# Mergen_Ground_Station_V2_0.net
KiCad netlist of a schematic drawn in EAGLE
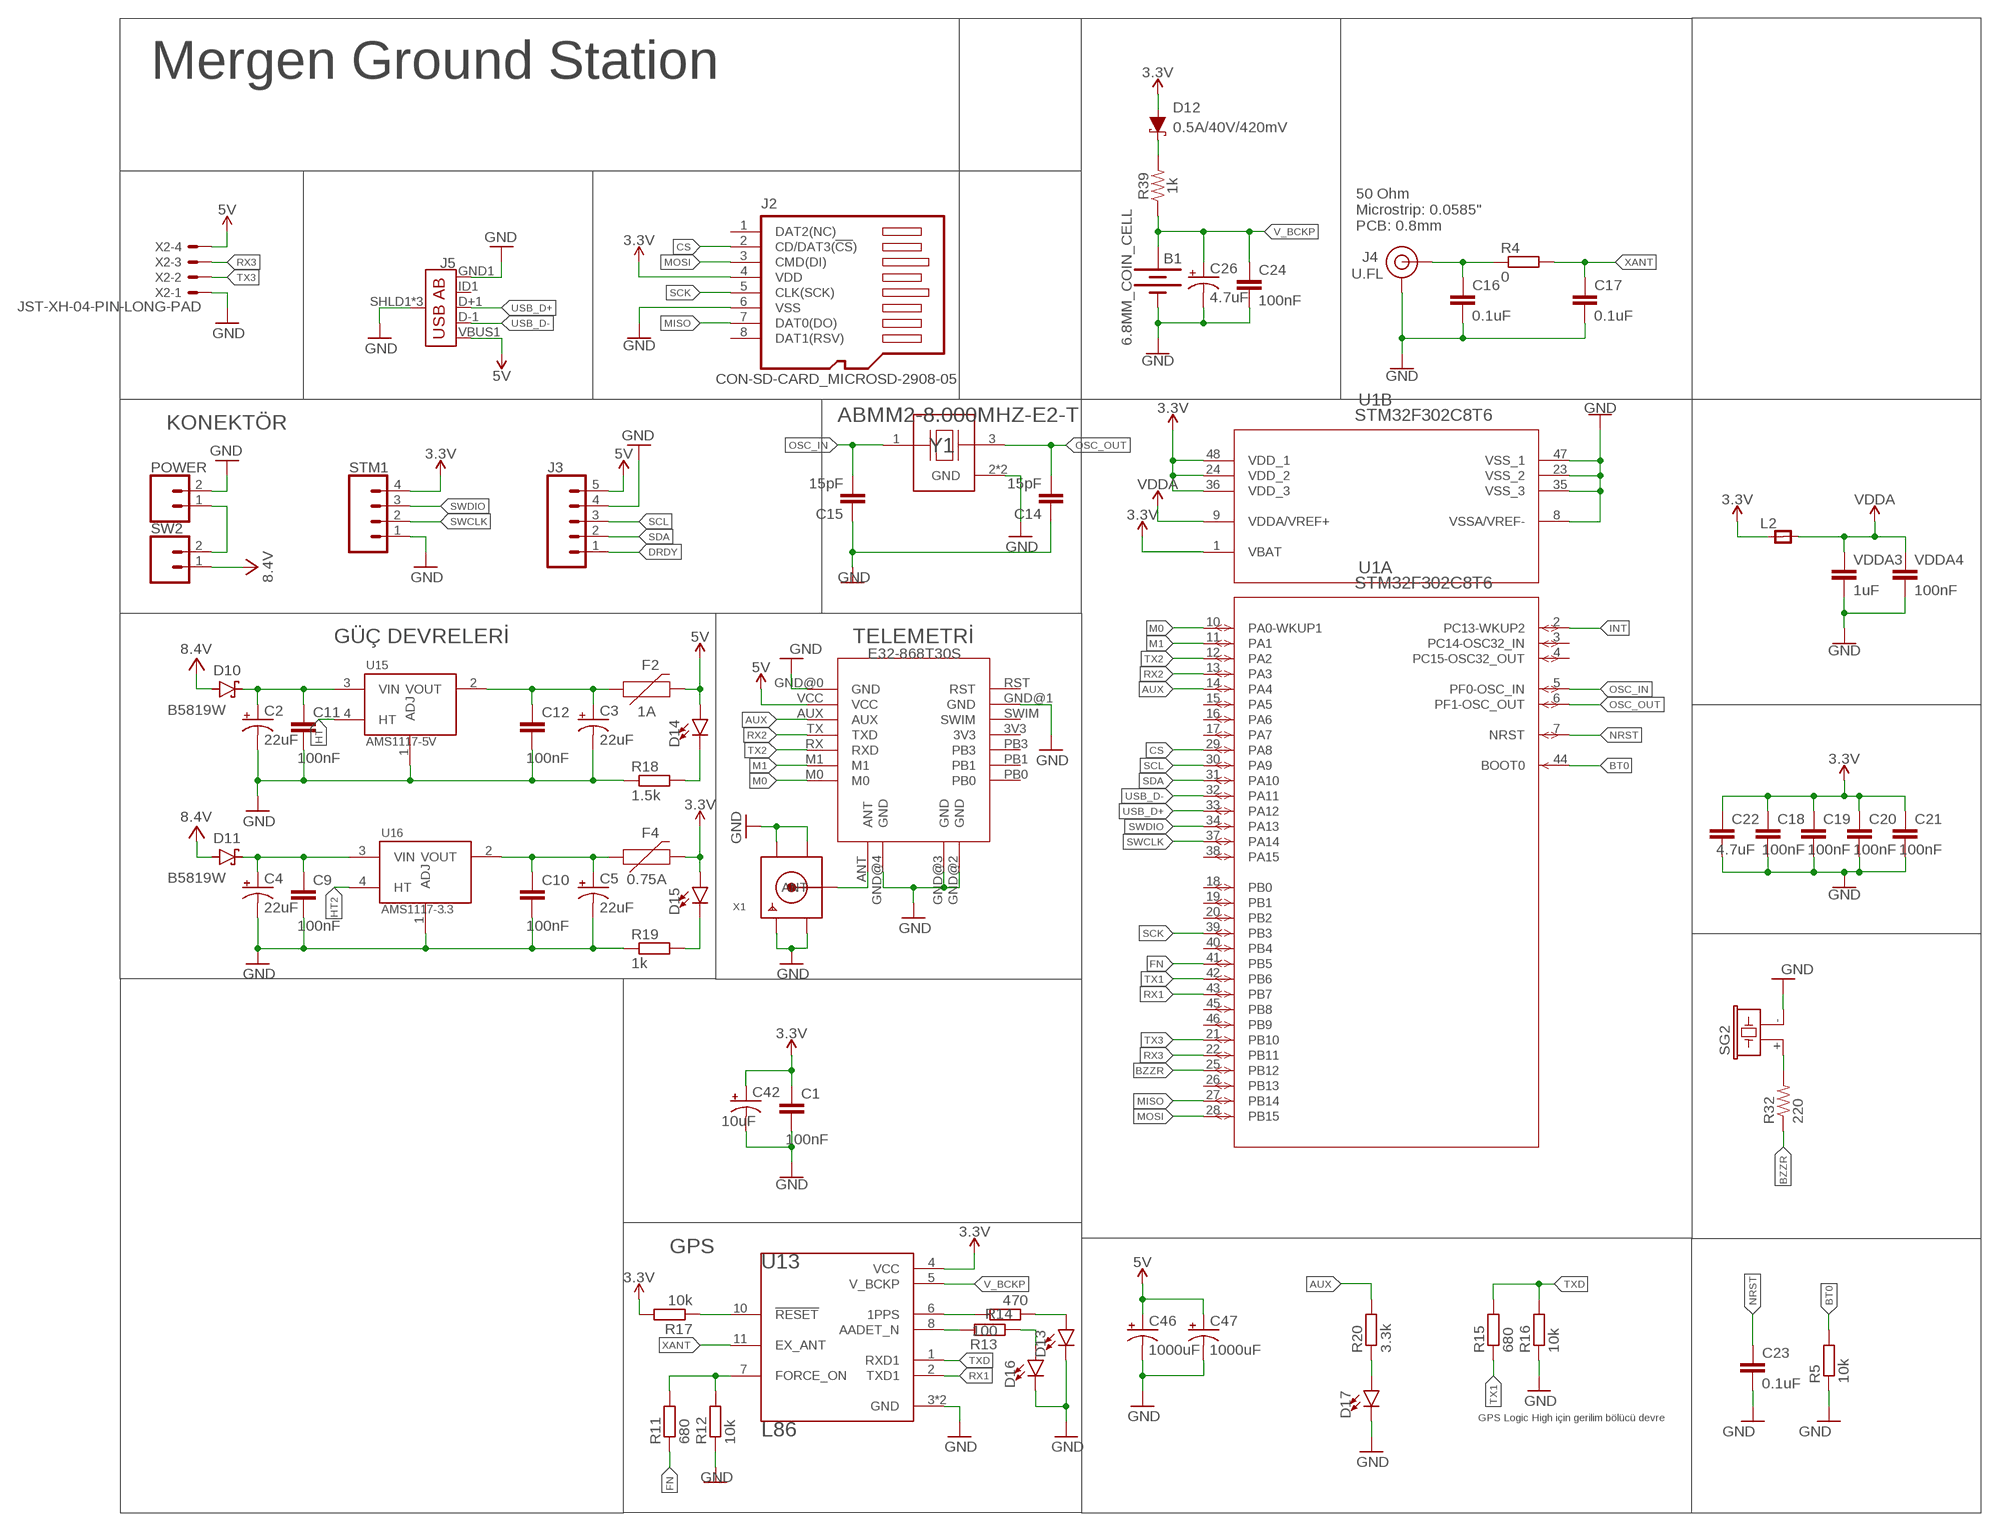
[diagram p0: schematic, sheet 1]

(export (version "E")
  (design (tool "Eeschema 10.0.6"))
  (components
    (comp (ref "B1")
      (value "6.8MM_COIN_CELL")
      (footprint "eagle-import:BATTCON-6.8MM")
      (libsource (lib "eagle-import") (part "BATTERY-6.8MM_SMD"))
    )
    (comp (ref "C1")
      (value "100nF")
      (footprint "eagle-import:C0603")
      (libsource (lib "eagle-import") (part "C-EUC0603"))
    )
    (comp (ref "C2")
      (value "22uF")
      (footprint "eagle-import:CT3528")
      (libsource (lib "eagle-import") (part "rcl_334_CPOL-USCT3528"))
    )
    (comp (ref "C3")
      (value "22uF")
      (footprint "eagle-import:CT3528")
      (libsource (lib "eagle-import") (part "rcl_334_CPOL-USCT3528"))
    )
    (comp (ref "C4")
      (value "22uF")
      (footprint "eagle-import:CT3528")
      (libsource (lib "eagle-import") (part "rcl_334_CPOL-USCT3528"))
    )
    (comp (ref "C5")
      (value "22uF")
      (footprint "eagle-import:CT3528")
      (libsource (lib "eagle-import") (part "rcl_334_CPOL-USCT3528"))
    )
    (comp (ref "C9")
      (value "100nF")
      (footprint "eagle-import:C0603")
      (libsource (lib "eagle-import") (part "C-EUC0603"))
    )
    (comp (ref "C10")
      (value "100nF")
      (footprint "eagle-import:C0603")
      (libsource (lib "eagle-import") (part "C-EUC0603"))
    )
    (comp (ref "C11")
      (value "100nF")
      (footprint "eagle-import:C0603")
      (libsource (lib "eagle-import") (part "C-EUC0603"))
    )
    (comp (ref "C12")
      (value "100nF")
      (footprint "eagle-import:C0603")
      (libsource (lib "eagle-import") (part "C-EUC0603"))
    )
    (comp (ref "C14")
      (value "15pF")
      (footprint "eagle-import:C0603")
      (libsource (lib "eagle-import") (part "C-EUC0603"))
    )
    (comp (ref "C15")
      (value "15pF")
      (footprint "eagle-import:C0603")
      (libsource (lib "eagle-import") (part "C-EUC0603"))
    )
    (comp (ref "C16")
      (value "0.1uF")
      (footprint "eagle-import:C0603")
      (libsource (lib "eagle-import") (part "C-EUC0603"))
    )
    (comp (ref "C17")
      (value "0.1uF")
      (footprint "eagle-import:C0603")
      (libsource (lib "eagle-import") (part "C-EUC0603"))
    )
    (comp (ref "C18")
      (value "100nF")
      (footprint "eagle-import:C0603")
      (libsource (lib "eagle-import") (part "C-EUC0603"))
    )
    (comp (ref "C19")
      (value "100nF")
      (footprint "eagle-import:C0603")
      (libsource (lib "eagle-import") (part "C-EUC0603"))
    )
    (comp (ref "C20")
      (value "100nF")
      (footprint "eagle-import:C0603")
      (libsource (lib "eagle-import") (part "C-EUC0603"))
    )
    (comp (ref "C21")
      (value "100nF")
      (footprint "eagle-import:C0603")
      (libsource (lib "eagle-import") (part "C-EUC0603"))
    )
    (comp (ref "C22")
      (value "4.7uF")
      (footprint "eagle-import:C0603")
      (libsource (lib "eagle-import") (part "C-EUC0603"))
    )
    (comp (ref "C23")
      (value "0.1uF")
      (footprint "eagle-import:C0603")
      (libsource (lib "eagle-import") (part "C-EUC0603"))
    )
    (comp (ref "C24")
      (value "100nF")
      (footprint "eagle-import:C0603")
      (libsource (lib "eagle-import") (part "C-EUC0603"))
    )
    (comp (ref "C26")
      (value "4.7uF")
      (footprint "eagle-import:A_3216-18R")
      (libsource (lib "eagle-import") (part "rcl_334_CPOL-USA/3216-18R"))
    )
    (comp (ref "C42")
      (value "10uF")
      (footprint "eagle-import:EIA3216")
      (libsource (lib "eagle-import") (part "10UF-POLAR-EIA3216-16V-10%(TANT)"))
    )
    (comp (ref "C46")
      (value "1000uF")
      (footprint "eagle-import:150CLZ-1010")
      (libsource (lib "eagle-import") (part "CPOL-US150CLZ-1010"))
    )
    (comp (ref "C47")
      (value "1000uF")
      (footprint "eagle-import:150CLZ-1010")
      (libsource (lib "eagle-import") (part "CPOL-US150CLZ-1010"))
    )
    (comp (ref "D10")
      (value "B5819W")
      (footprint "eagle-import:SODFL3718X115")
      (fields (field (name "MANUFACTURER") "ON Semiconductor") (field (name "MPN") "MBR0520LT1G"))
      (libsource (lib "eagle-import") (part "SCHOTTKY_DO-219MBR0520LT1G"))
    )
    (comp (ref "D11")
      (value "B5819W")
      (footprint "eagle-import:SODFL3718X115")
      (fields (field (name "MANUFACTURER") "ON Semiconductor") (field (name "MPN") "MBR0520LT1G"))
      (libsource (lib "eagle-import") (part "SCHOTTKY_DO-219MBR0520LT1G"))
    )
    (comp (ref "D12")
      (value "0.5A/40V/420mV")
      (footprint "eagle-import:SOD-323")
      (libsource (lib "eagle-import") (part "DIODE-SCHOTTKY-PMEG4005EJ"))
    )
    (comp (ref "D13")
      (value "LED0603")
      (footprint "eagle-import:LED-0603")
      (libsource (lib "eagle-import") (part "LED0603"))
    )
    (comp (ref "D14")
      (value "LED0603")
      (footprint "eagle-import:LED-0603")
      (libsource (lib "eagle-import") (part "LED0603"))
    )
    (comp (ref "D15")
      (value "LED0603")
      (footprint "eagle-import:LED-0603")
      (libsource (lib "eagle-import") (part "LED0603"))
    )
    (comp (ref "D16")
      (value "LED0603")
      (footprint "eagle-import:LED-0603")
      (libsource (lib "eagle-import") (part "LED0603"))
    )
    (comp (ref "D17")
      (value "LED0603")
      (footprint "eagle-import:LED-0603")
      (libsource (lib "eagle-import") (part "LED0603"))
    )
    (comp (ref "F2")
      (value "1A")
      (footprint "eagle-import:1206")
      (libsource (lib "eagle-import") (part "PPTC_HALF-AMP"))
    )
    (comp (ref "F4")
      (value "0.75A")
      (footprint "eagle-import:1206")
      (libsource (lib "eagle-import") (part "PPTC_HALF-AMP"))
    )
    (comp (ref "J2")
      (value "CON-SD-CARD_MICROSD-2908-05")
      (footprint "eagle-import:CON-SD-CARD_2908-05")
      (libsource (lib "eagle-import") (part "CON-SD-CARD_MICROSD-2908-05"))
    )
    (comp (ref "J3")
      (value "CONN_05LOCK_LONGPADS")
      (footprint "eagle-import:1X05_LOCK_LONGPADS")
      (libsource (lib "eagle-import") (part "CONN_05LOCK_LONGPADS"))
    )
    (comp (ref "J4")
      (value "U.FL")
      (footprint "eagle-import:U.FL")
      (libsource (lib "eagle-import") (part "U.FL2PIN"))
    )
    (comp (ref "J5")
      (value "USB_AB_SMT")
      (footprint "eagle-import:USB-AB-MICRO-SMD")
      (libsource (lib "eagle-import") (part "USB_AB_SMT"))
    )
    (comp (ref "L2")
      (value "RC-MASTER-SMD_FB_0805MP")
      (footprint "eagle-import:RC-MASTER-SMD_L0805MP")
      (libsource (lib "eagle-import") (part "RC-MASTER-SMD_FB_0805MP"))
    )
    (comp (ref "POWER")
      (value "CONN_023.5MM-NO_SILK")
      (footprint "eagle-import:SCREWTERMINAL-3.5MM-2-NS")
      (libsource (lib "eagle-import") (part "CONN_023.5MM-NO_SILK"))
    )
    (comp (ref "R4")
      (value "0")
      (footprint "eagle-import:R0603")
      (libsource (lib "eagle-import") (part "R-EU_R0603"))
    )
    (comp (ref "R5")
      (value "10k")
      (footprint "eagle-import:R0603")
      (libsource (lib "eagle-import") (part "R-EU_R0603"))
    )
    (comp (ref "R11")
      (value "680")
      (footprint "eagle-import:R0603")
      (libsource (lib "eagle-import") (part "R-EU_R0603"))
    )
    (comp (ref "R12")
      (value "10k")
      (footprint "eagle-import:R0603")
      (libsource (lib "eagle-import") (part "R-EU_R0603"))
    )
    (comp (ref "R13")
      (value "100")
      (footprint "eagle-import:R0603")
      (libsource (lib "eagle-import") (part "R-EU_R0603"))
    )
    (comp (ref "R14")
      (value "470")
      (footprint "eagle-import:R0603")
      (libsource (lib "eagle-import") (part "R-EU_R0603"))
    )
    (comp (ref "R15")
      (value "680")
      (footprint "eagle-import:R0603")
      (libsource (lib "eagle-import") (part "R-EU_R0603"))
    )
    (comp (ref "R16")
      (value "10k")
      (footprint "eagle-import:R0603")
      (libsource (lib "eagle-import") (part "R-EU_R0603"))
    )
    (comp (ref "R17")
      (value "10k")
      (footprint "eagle-import:R0603")
      (libsource (lib "eagle-import") (part "R-EU_R0603"))
    )
    (comp (ref "R18")
      (value "1.5k")
      (footprint "eagle-import:R0603")
      (libsource (lib "eagle-import") (part "R-EU_R0603"))
    )
    (comp (ref "R19")
      (value "1k")
      (footprint "eagle-import:R0603")
      (libsource (lib "eagle-import") (part "R-EU_R0603"))
    )
    (comp (ref "R20")
      (value "3.3k")
      (footprint "eagle-import:R0603")
      (libsource (lib "eagle-import") (part "R-EU_R0603"))
    )
    (comp (ref "R32")
      (value "220")
      (footprint "eagle-import:0603")
      (libsource (lib "eagle-import") (part "0OHM-0603-1/10W-5%"))
    )
    (comp (ref "R39")
      (value "1k")
      (footprint "eagle-import:0603")
      (libsource (lib "eagle-import") (part "1KOHM-0603-1/10W-1%"))
    )
    (comp (ref "SG2")
      (value "F/CM12P")
      (footprint "eagle-import:F_CM12P")
      (libsource (lib "eagle-import") (part "F/CM12P"))
    )
    (comp (ref "STM1")
      (value "CONN_04")
      (footprint "eagle-import:1X04")
      (libsource (lib "eagle-import") (part "CONN_04"))
    )
    (comp (ref "SW2")
      (value "CONN_023.5MM-NO_SILK")
      (footprint "eagle-import:SCREWTERMINAL-3.5MM-2-NS")
      (libsource (lib "eagle-import") (part "CONN_023.5MM-NO_SILK"))
    )
    (comp (ref "U1")
      (value "STM32F302C8T6")
      (footprint "eagle-import:LQFP48-7X7MM")
      (fields (field (name "COPYRIGHT") "Copyright (C) 2018 Accelerated Designs. All rights reserved"))
      (libsource (lib "eagle-import") (part "STM32F302C8T6"))
    )
    (comp (ref "U13")
      (value "L86")
      (footprint "eagle-import:XCVR_L86")
      (fields (field (name "MF") "Quectel"))
      (libsource (lib "eagle-import") (part "L86"))
    )
    (comp (ref "U14")
      (value "E32-868T30S")
      (footprint "eagle-import:E32-868T30S")
      (libsource (lib "eagle-import") (part "E32-868T30S"))
    )
    (comp (ref "U15")
      (value "AMS1117-5V")
      (footprint "eagle-import:SOT229P700X180-4N")
      (fields (field (name "MF") "Advanced Monolithic Systems") (field (name "MP") "AMS1117-3.3"))
      (libsource (lib "eagle-import") (part "AMS1117-3.3"))
    )
    (comp (ref "U16")
      (value "AMS1117-3.3")
      (footprint "eagle-import:SOT229P700X180-4N")
      (fields (field (name "MF") "Advanced Monolithic Systems"))
      (libsource (lib "eagle-import") (part "AMS1117-3.3"))
    )
    (comp (ref "VDDA3")
      (value "1uF")
      (footprint "eagle-import:0603")
      (libsource (lib "eagle-import") (part "0.1UF-0603-25V-(+80/-20%)"))
    )
    (comp (ref "VDDA4")
      (value "100nF")
      (footprint "eagle-import:0603")
      (libsource (lib "eagle-import") (part "0.1UF-0603-25V-(+80/-20%)"))
    )
    (comp (ref "X1")
      (value "SMACONNECTOR")
      (footprint "eagle-import:SMA90_DIP")
      (libsource (lib "eagle-import") (part "SMACONNECTOR"))
    )
    (comp (ref "X2")
      (value "JST-XH-04-PIN-LONG-PAD")
      (footprint "eagle-import:JST-XH-04-PACKAGE-LONG-PAD")
      (libsource (lib "eagle-import") (part "JST-XH-04-PIN-LONG-PAD"))
    )
    (comp (ref "Y1")
      (value "ABMM2-8.000MHZ-E2-T")
      (footprint "eagle-import:XTAL_ABMM2-8.000MHZ-E2-T")
      (fields (field (name "MF") "Abracon"))
      (libsource (lib "eagle-import") (part "ABMM2-8.000MHZ-E2-T"))
    )
  )
  (nets
    (net (code "1") (name "3.3V") (class "Default")
      (node (ref "C1") (pin "1") (pinfunction "1_1") (pintype "passive"))
      (node (ref "C18") (pin "1") (pinfunction "1_1") (pintype "passive"))
      (node (ref "C19") (pin "1") (pinfunction "1_1") (pintype "passive"))
      (node (ref "C20") (pin "1") (pinfunction "1_1") (pintype "passive"))
      (node (ref "C21") (pin "1") (pinfunction "1_1") (pintype "passive"))
      (node (ref "C22") (pin "1") (pinfunction "1_1") (pintype "passive"))
      (node (ref "C42") (pin "+") (pinfunction "+_+") (pintype "passive"))
      (node (ref "D12") (pin "A") (pinfunction "A_A") (pintype "passive"))
      (node (ref "D15") (pin "A") (pinfunction "A_A") (pintype "passive"))
      (node (ref "F4") (pin "2") (pinfunction "2_2") (pintype "bidirectional"))
      (node (ref "J2") (pin "4") (pinfunction "VDD_4") (pintype "bidirectional"))
      (node (ref "L2") (pin "1") (pinfunction "1_1") (pintype "passive"))
      (node (ref "R17") (pin "2") (pinfunction "2_2") (pintype "passive"))
      (node (ref "STM1") (pin "4") (pinfunction "4_4") (pintype "passive"))
      (node (ref "U1") (pin "1") (pinfunction "VBAT_1") (pintype "power_in"))
      (node (ref "U1") (pin "24") (pinfunction "VDD_2_24") (pintype "power_in"))
      (node (ref "U1") (pin "36") (pinfunction "VDD_3_36") (pintype "power_in"))
      (node (ref "U1") (pin "48") (pinfunction "VDD_1_48") (pintype "power_in"))
      (node (ref "U13") (pin "4") (pinfunction "VCC_4") (pintype "power_in"))
    )
    (net (code "2") (name "5V") (class "Default")
      (node (ref "C46") (pin "+") (pinfunction "+_+") (pintype "passive"))
      (node (ref "C47") (pin "+") (pinfunction "+_+") (pintype "passive"))
      (node (ref "D14") (pin "A") (pinfunction "A_A") (pintype "passive"))
      (node (ref "F2") (pin "2") (pinfunction "2_2") (pintype "bidirectional"))
      (node (ref "J3") (pin "5") (pinfunction "5_5") (pintype "passive"))
      (node (ref "J5") (pin "VBUS1") (pinfunction "VBUS_VBUS1") (pintype "power_in"))
      (node (ref "U14") (pin "VCC") (pinfunction "VCC_VCC") (pintype "bidirectional"))
      (node (ref "X2") (pin "4") (pinfunction "S_4") (pintype "passive"))
    )
    (net (code "3") (name "8.4V") (class "Default")
      (node (ref "D10") (pin "2") (pinfunction "A_2") (pintype "passive"))
      (node (ref "D11") (pin "2") (pinfunction "A_2") (pintype "passive"))
      (node (ref "SW2") (pin "1") (pinfunction "1_1") (pintype "passive"))
    )
    (net (code "4") (name "AUX") (class "Default")
      (node (ref "R20") (pin "2") (pinfunction "2_2") (pintype "passive"))
      (node (ref "U1") (pin "14") (pinfunction "PA4_14") (pintype "bidirectional"))
      (node (ref "U14") (pin "AUX") (pinfunction "AUX_AUX") (pintype "bidirectional"))
    )
    (net (code "5") (name "BT0") (class "Default")
      (node (ref "R5") (pin "2") (pinfunction "2_2") (pintype "passive"))
      (node (ref "U1") (pin "44") (pinfunction "BOOT0_44") (pintype "input"))
    )
    (net (code "6") (name "BZZR") (class "Default")
      (node (ref "R32") (pin "1") (pinfunction "1_1") (pintype "passive"))
      (node (ref "U1") (pin "25") (pinfunction "PB12_25") (pintype "bidirectional"))
    )
    (net (code "7") (name "CS") (class "Default")
      (node (ref "J2") (pin "2") (pinfunction "CD/DAT3(~{CS})_2") (pintype "bidirectional"))
      (node (ref "U1") (pin "29") (pinfunction "PA8_29") (pintype "bidirectional"))
    )
    (net (code "8") (name "DRDY") (class "Default")
      (node (ref "J3") (pin "1") (pinfunction "1_1") (pintype "passive"))
    )
    (net (code "9") (name "FN") (class "Default")
      (node (ref "R11") (pin "1") (pinfunction "1_1") (pintype "passive"))
      (node (ref "U1") (pin "41") (pinfunction "PB5_41") (pintype "bidirectional"))
    )
    (net (code "10") (name "GND") (class "Default")
      (node (ref "B1") (pin "-") (pinfunction "-_-") (pintype "power_in"))
      (node (ref "C1") (pin "2") (pinfunction "2_2") (pintype "passive"))
      (node (ref "C10") (pin "2") (pinfunction "2_2") (pintype "passive"))
      (node (ref "C11") (pin "2") (pinfunction "2_2") (pintype "passive"))
      (node (ref "C12") (pin "2") (pinfunction "2_2") (pintype "passive"))
      (node (ref "C14") (pin "1") (pinfunction "1_1") (pintype "passive"))
      (node (ref "C15") (pin "1") (pinfunction "1_1") (pintype "passive"))
      (node (ref "C16") (pin "2") (pinfunction "2_2") (pintype "passive"))
      (node (ref "C17") (pin "2") (pinfunction "2_2") (pintype "passive"))
      (node (ref "C18") (pin "2") (pinfunction "2_2") (pintype "passive"))
      (node (ref "C19") (pin "2") (pinfunction "2_2") (pintype "passive"))
      (node (ref "C2") (pin "-") (pinfunction "-_-") (pintype "passive"))
      (node (ref "C20") (pin "2") (pinfunction "2_2") (pintype "passive"))
      (node (ref "C21") (pin "2") (pinfunction "2_2") (pintype "passive"))
      (node (ref "C22") (pin "2") (pinfunction "2_2") (pintype "passive"))
      (node (ref "C23") (pin "2") (pinfunction "2_2") (pintype "passive"))
      (node (ref "C24") (pin "2") (pinfunction "2_2") (pintype "passive"))
      (node (ref "C26") (pin "-") (pinfunction "-_-") (pintype "passive"))
      (node (ref "C3") (pin "-") (pinfunction "-_-") (pintype "passive"))
      (node (ref "C4") (pin "-") (pinfunction "-_-") (pintype "passive"))
      (node (ref "C42") (pin "-") (pinfunction "-_-") (pintype "passive"))
      (node (ref "C46") (pin "-") (pinfunction "-_-") (pintype "passive"))
      (node (ref "C47") (pin "-") (pinfunction "-_-") (pintype "passive"))
      (node (ref "C5") (pin "-") (pinfunction "-_-") (pintype "passive"))
      (node (ref "C9") (pin "2") (pinfunction "2_2") (pintype "passive"))
      (node (ref "D13") (pin "C") (pinfunction "C_C") (pintype "passive"))
      (node (ref "D16") (pin "C") (pinfunction "C_C") (pintype "passive"))
      (node (ref "D17") (pin "C") (pinfunction "C_C") (pintype "passive"))
      (node (ref "J2") (pin "6") (pinfunction "VSS_6") (pintype "bidirectional"))
      (node (ref "J3") (pin "4") (pinfunction "4_4") (pintype "passive"))
      (node (ref "J4") (pin "1") (pinfunction "GND_1") (pintype "bidirectional"))
      (node (ref "J4") (pin "2") (pinfunction "GND_2") (pintype "bidirectional"))
      (node (ref "J5") (pin "GND1") (pinfunction "GND_GND1") (pintype "power_in"))
      (node (ref "J5") (pin "SHLD1") (pinfunction "SHIELD_SHLD1") (pintype "bidirectional"))
      (node (ref "J5") (pin "SHLD2") (pinfunction "SHIELD_SHLD2") (pintype "bidirectional"))
      (node (ref "J5") (pin "SHLD3") (pinfunction "SHIELD_SHLD3") (pintype "bidirectional"))
      (node (ref "POWER") (pin "2") (pinfunction "2_2") (pintype "passive"))
      (node (ref "R12") (pin "1") (pinfunction "1_1") (pintype "passive"))
      (node (ref "R16") (pin "1") (pinfunction "1_1") (pintype "passive"))
      (node (ref "R18") (pin "1") (pinfunction "1_1") (pintype "passive"))
      (node (ref "R19") (pin "1") (pinfunction "1_1") (pintype "passive"))
      (node (ref "R5") (pin "1") (pinfunction "1_1") (pintype "passive"))
      (node (ref "SG2") (pin "-") (pinfunction "2_-") (pintype "passive"))
      (node (ref "STM1") (pin "1") (pinfunction "1_1") (pintype "passive"))
      (node (ref "U1") (pin "23") (pinfunction "VSS_2_23") (pintype "power_in"))
      (node (ref "U1") (pin "35") (pinfunction "VSS_3_35") (pintype "power_in"))
      (node (ref "U1") (pin "47") (pinfunction "VSS_1_47") (pintype "power_in"))
      (node (ref "U1") (pin "8") (pinfunction "VSSA/VREF-_8") (pintype "power_in"))
      (node (ref "U13") (pin "12") (pinfunction "GND_12") (pintype "passive"))
      (node (ref "U13") (pin "3") (pinfunction "GND_3") (pintype "passive"))
      (node (ref "U14") (pin "GND@0") (pinfunction "GND_GND@0") (pintype "bidirectional"))
      (node (ref "U14") (pin "GND@1") (pinfunction "GND_GND@1") (pintype "bidirectional"))
      (node (ref "U14") (pin "GND@2") (pinfunction "GND_GND@2") (pintype "bidirectional"))
      (node (ref "U14") (pin "GND@3") (pinfunction "GND_GND@3") (pintype "bidirectional"))
      (node (ref "U14") (pin "GND@4") (pinfunction "GND_GND@4") (pintype "bidirectional"))
      (node (ref "U15") (pin "1") (pinfunction "ADJ_1") (pintype "power_in"))
      (node (ref "U16") (pin "1") (pinfunction "ADJ_1") (pintype "power_in"))
      (node (ref "VDDA3") (pin "2") (pinfunction "2_2") (pintype "passive"))
      (node (ref "VDDA4") (pin "2") (pinfunction "2_2") (pintype "passive"))
      (node (ref "X1") (pin "GND1") (pinfunction "GND1_GND1") (pintype "power_in"))
      (node (ref "X1") (pin "GND2") (pinfunction "GND2_GND2") (pintype "power_in"))
      (node (ref "X1") (pin "GND3") (pinfunction "GND3_GND3") (pintype "power_in"))
      (node (ref "X1") (pin "GND4") (pinfunction "GND4_GND4") (pintype "power_in"))
      (node (ref "X2") (pin "1") (pinfunction "S_1") (pintype "passive"))
      (node (ref "Y1") (pin "2") (pinfunction "GND_2") (pintype "power_in"))
      (node (ref "Y1") (pin "4") (pinfunction "GND_4") (pintype "power_in"))
    )
    (net (code "11") (name "HT") (class "Default")
      (node (ref "U15") (pin "4") (pinfunction "HT_4") (pintype "bidirectional"))
    )
    (net (code "12") (name "HT2") (class "Default")
      (node (ref "U16") (pin "4") (pinfunction "HT_4") (pintype "bidirectional"))
    )
    (net (code "13") (name "INT") (class "Default")
      (node (ref "U1") (pin "2") (pinfunction "PC13-WKUP2_2") (pintype "bidirectional"))
    )
    (net (code "14") (name "M0") (class "Default")
      (node (ref "U1") (pin "10") (pinfunction "PA0-WKUP1_10") (pintype "bidirectional"))
      (node (ref "U14") (pin "M0") (pinfunction "M0_M0") (pintype "bidirectional"))
    )
    (net (code "15") (name "M1") (class "Default")
      (node (ref "U1") (pin "11") (pinfunction "PA1_11") (pintype "bidirectional"))
      (node (ref "U14") (pin "M1") (pinfunction "M1_M1") (pintype "bidirectional"))
    )
    (net (code "16") (name "MISO") (class "Default")
      (node (ref "J2") (pin "7") (pinfunction "DAT0(DO)_7") (pintype "bidirectional"))
      (node (ref "U1") (pin "27") (pinfunction "PB14_27") (pintype "bidirectional"))
    )
    (net (code "17") (name "MOSI") (class "Default")
      (node (ref "J2") (pin "3") (pinfunction "CMD(DI)_3") (pintype "bidirectional"))
      (node (ref "U1") (pin "28") (pinfunction "PB15_28") (pintype "bidirectional"))
    )
    (net (code "18") (name "NRST") (class "Default")
      (node (ref "C23") (pin "1") (pinfunction "1_1") (pintype "passive"))
      (node (ref "U1") (pin "7") (pinfunction "NRST_7") (pintype "bidirectional"))
    )
    (net (code "19") (name "Net-(D10-C)") (class "Default")
      (node (ref "C11") (pin "1") (pinfunction "1_1") (pintype "passive"))
      (node (ref "C2") (pin "+") (pinfunction "+_+") (pintype "passive"))
      (node (ref "D10") (pin "1") (pinfunction "C_1") (pintype "passive"))
      (node (ref "U15") (pin "3") (pinfunction "VIN_3") (pintype "input"))
    )
    (net (code "20") (name "Net-(D11-C)") (class "Default")
      (node (ref "C4") (pin "+") (pinfunction "+_+") (pintype "passive"))
      (node (ref "C9") (pin "1") (pinfunction "1_1") (pintype "passive"))
      (node (ref "D11") (pin "1") (pinfunction "C_1") (pintype "passive"))
      (node (ref "U16") (pin "3") (pinfunction "VIN_3") (pintype "input"))
    )
    (net (code "21") (name "Net-(D12-PadC)") (class "Default")
      (node (ref "D12") (pin "C") (pinfunction "C_C") (pintype "passive"))
      (node (ref "R39") (pin "2") (pinfunction "2_2") (pintype "passive"))
    )
    (net (code "22") (name "Net-(D13-PadA)") (class "Default")
      (node (ref "D13") (pin "A") (pinfunction "A_A") (pintype "passive"))
      (node (ref "R14") (pin "1") (pinfunction "1_1") (pintype "passive"))
    )
    (net (code "23") (name "Net-(D14-PadC)") (class "Default")
      (node (ref "D14") (pin "C") (pinfunction "C_C") (pintype "passive"))
      (node (ref "R18") (pin "2") (pinfunction "2_2") (pintype "passive"))
    )
    (net (code "24") (name "Net-(D15-PadC)") (class "Default")
      (node (ref "D15") (pin "C") (pinfunction "C_C") (pintype "passive"))
      (node (ref "R19") (pin "2") (pinfunction "2_2") (pintype "passive"))
    )
    (net (code "25") (name "Net-(D16-PadA)") (class "Default")
      (node (ref "D16") (pin "A") (pinfunction "A_A") (pintype "passive"))
      (node (ref "R13") (pin "1") (pinfunction "1_1") (pintype "passive"))
    )
    (net (code "26") (name "Net-(D17-PadA)") (class "Default")
      (node (ref "D17") (pin "A") (pinfunction "A_A") (pintype "passive"))
      (node (ref "R20") (pin "1") (pinfunction "1_1") (pintype "passive"))
    )
    (net (code "27") (name "Net-(J4-SIGNAL)") (class "Default")
      (node (ref "C16") (pin "1") (pinfunction "1_1") (pintype "passive"))
      (node (ref "J4") (pin "FEED") (pinfunction "SIGNAL_FEED") (pintype "bidirectional"))
      (node (ref "R4") (pin "1") (pinfunction "1_1") (pintype "passive"))
    )
    (net (code "28") (name "Net-(POWER-Pad1)") (class "Default")
      (node (ref "POWER") (pin "1") (pinfunction "1_1") (pintype "passive"))
      (node (ref "SW2") (pin "2") (pinfunction "2_2") (pintype "passive"))
    )
    (net (code "29") (name "Net-(SG2-1)") (class "Default")
      (node (ref "R32") (pin "2") (pinfunction "2_2") (pintype "passive"))
      (node (ref "SG2") (pin "+") (pinfunction "1_+") (pintype "passive"))
    )
    (net (code "30") (name "Net-(U13-1PPS)") (class "Default")
      (node (ref "R14") (pin "2") (pinfunction "2_2") (pintype "passive"))
      (node (ref "U13") (pin "6") (pinfunction "1PPS_6") (pintype "output"))
    )
    (net (code "31") (name "Net-(U13-AADET_N)") (class "Default")
      (node (ref "R13") (pin "2") (pinfunction "2_2") (pintype "passive"))
      (node (ref "U13") (pin "8") (pinfunction "AADET_N_8") (pintype "output"))
    )
    (net (code "32") (name "Net-(U13-FORCE_ON)") (class "Default")
      (node (ref "R11") (pin "2") (pinfunction "2_2") (pintype "passive"))
      (node (ref "R12") (pin "2") (pinfunction "2_2") (pintype "passive"))
      (node (ref "U13") (pin "7") (pinfunction "FORCE_ON_7") (pintype "input"))
    )
    (net (code "33") (name "Net-(U13-~{RESET})") (class "Default")
      (node (ref "R17") (pin "1") (pinfunction "1_1") (pintype "passive"))
      (node (ref "U13") (pin "10") (pinfunction "~{RESET}_10") (pintype "input"))
    )
    (net (code "34") (name "Net-(U15-VOUT)") (class "Default")
      (node (ref "C12") (pin "1") (pinfunction "1_1") (pintype "passive"))
      (node (ref "C3") (pin "+") (pinfunction "+_+") (pintype "passive"))
      (node (ref "F2") (pin "1") (pinfunction "1_1") (pintype "bidirectional"))
      (node (ref "U15") (pin "2") (pinfunction "VOUT_2") (pintype "output"))
    )
    (net (code "35") (name "Net-(U16-VOUT)") (class "Default")
      (node (ref "C10") (pin "1") (pinfunction "1_1") (pintype "passive"))
      (node (ref "C5") (pin "+") (pinfunction "+_+") (pintype "passive"))
      (node (ref "F4") (pin "1") (pinfunction "1_1") (pintype "bidirectional"))
      (node (ref "U16") (pin "2") (pinfunction "VOUT_2") (pintype "output"))
    )
    (net (code "36") (name "Net-(X1-ANT)") (class "Default")
      (node (ref "U14") (pin "ANT") (pinfunction "ANT_ANT") (pintype "bidirectional"))
      (node (ref "X1") (pin "ANTENNA") (pinfunction "ANT_ANTENNA") (pintype "bidirectional"))
    )
    (net (code "37") (name "OSC_IN") (class "Default")
      (node (ref "C15") (pin "2") (pinfunction "2_2") (pintype "passive"))
      (node (ref "U1") (pin "5") (pinfunction "PF0-OSC_IN_5") (pintype "bidirectional"))
      (node (ref "Y1") (pin "1") (pinfunction "1_1") (pintype "passive"))
    )
    (net (code "38") (name "OSC_OUT") (class "Default")
      (node (ref "C14") (pin "2") (pinfunction "2_2") (pintype "passive"))
      (node (ref "U1") (pin "6") (pinfunction "PF1-OSC_OUT_6") (pintype "bidirectional"))
      (node (ref "Y1") (pin "3") (pinfunction "3_3") (pintype "passive"))
    )
    (net (code "39") (name "RX1") (class "Default")
      (node (ref "U1") (pin "43") (pinfunction "PB7_43") (pintype "bidirectional"))
      (node (ref "U13") (pin "2") (pinfunction "TXD1_2") (pintype "output"))
    )
    (net (code "40") (name "RX2") (class "Default")
      (node (ref "U1") (pin "13") (pinfunction "PA3_13") (pintype "bidirectional"))
      (node (ref "U14") (pin "TX") (pinfunction "TXD_TX") (pintype "bidirectional"))
    )
    (net (code "41") (name "RX3") (class "Default")
      (node (ref "U1") (pin "22") (pinfunction "PB11_22") (pintype "bidirectional"))
      (node (ref "X2") (pin "3") (pinfunction "S_3") (pintype "passive"))
    )
    (net (code "42") (name "SCK") (class "Default")
      (node (ref "J2") (pin "5") (pinfunction "CLK(SCK)_5") (pintype "bidirectional"))
      (node (ref "U1") (pin "39") (pinfunction "PB3_39") (pintype "bidirectional"))
    )
    (net (code "43") (name "SCL") (class "Default")
      (node (ref "J3") (pin "3") (pinfunction "3_3") (pintype "passive"))
      (node (ref "U1") (pin "30") (pinfunction "PA9_30") (pintype "bidirectional"))
    )
    (net (code "44") (name "SDA") (class "Default")
      (node (ref "J3") (pin "2") (pinfunction "2_2") (pintype "passive"))
      (node (ref "U1") (pin "31") (pinfunction "PA10_31") (pintype "bidirectional"))
    )
    (net (code "45") (name "SWCLK") (class "Default")
      (node (ref "STM1") (pin "2") (pinfunction "2_2") (pintype "passive"))
      (node (ref "U1") (pin "37") (pinfunction "PA14_37") (pintype "bidirectional"))
    )
    (net (code "46") (name "SWDIO") (class "Default")
      (node (ref "STM1") (pin "3") (pinfunction "3_3") (pintype "passive"))
      (node (ref "U1") (pin "34") (pinfunction "PA13_34") (pintype "bidirectional"))
    )
    (net (code "47") (name "TX1") (class "Default")
      (node (ref "R15") (pin "1") (pinfunction "1_1") (pintype "passive"))
      (node (ref "U1") (pin "42") (pinfunction "PB6_42") (pintype "bidirectional"))
    )
    (net (code "48") (name "TX2") (class "Default")
      (node (ref "U1") (pin "12") (pinfunction "PA2_12") (pintype "bidirectional"))
      (node (ref "U14") (pin "RX") (pinfunction "RXD_RX") (pintype "bidirectional"))
    )
    (net (code "49") (name "TX3") (class "Default")
      (node (ref "U1") (pin "21") (pinfunction "PB10_21") (pintype "bidirectional"))
      (node (ref "X2") (pin "2") (pinfunction "S_2") (pintype "passive"))
    )
    (net (code "50") (name "TXD") (class "Default")
      (node (ref "R15") (pin "2") (pinfunction "2_2") (pintype "passive"))
      (node (ref "R16") (pin "2") (pinfunction "2_2") (pintype "passive"))
      (node (ref "U13") (pin "1") (pinfunction "RXD1_1") (pintype "input"))
    )
    (net (code "51") (name "USB_D+") (class "Default")
      (node (ref "J5") (pin "D+1") (pinfunction "D+_D+1") (pintype "bidirectional"))
      (node (ref "U1") (pin "33") (pinfunction "PA12_33") (pintype "bidirectional"))
    )
    (net (code "52") (name "USB_D-") (class "Default")
      (node (ref "J5") (pin "D-1") (pinfunction "D-_D-1") (pintype "bidirectional"))
      (node (ref "U1") (pin "32") (pinfunction "PA11_32") (pintype "bidirectional"))
    )
    (net (code "53") (name "VDDA") (class "Default")
      (node (ref "L2") (pin "2") (pinfunction "2_2") (pintype "passive"))
      (node (ref "U1") (pin "9") (pinfunction "VDDA/VREF+_9") (pintype "power_in"))
      (node (ref "VDDA3") (pin "1") (pinfunction "1_1") (pintype "passive"))
      (node (ref "VDDA4") (pin "1") (pinfunction "1_1") (pintype "passive"))
    )
    (net (code "54") (name "V_BCKP") (class "Default")
      (node (ref "B1") (pin "+") (pinfunction "+_+") (pintype "power_in"))
      (node (ref "C24") (pin "1") (pinfunction "1_1") (pintype "passive"))
      (node (ref "C26") (pin "+") (pinfunction "+_+") (pintype "passive"))
      (node (ref "R39") (pin "1") (pinfunction "1_1") (pintype "passive"))
      (node (ref "U13") (pin "5") (pinfunction "V_BCKP_5") (pintype "power_in"))
    )
    (net (code "55") (name "XANT") (class "Default")
      (node (ref "C17") (pin "1") (pinfunction "1_1") (pintype "passive"))
      (node (ref "R4") (pin "2") (pinfunction "2_2") (pintype "passive"))
      (node (ref "U13") (pin "11") (pinfunction "EX_ANT_11") (pintype "input"))
    )
    (net (code "56") (name "unconnected-(J2B-DAT1(RSV)-Pad8)") (class "Default")
      (node (ref "J2") (pin "8") (pinfunction "DAT1(RSV)_8") (pintype "bidirectional"))
    )
    (net (code "57") (name "unconnected-(J2B-DAT2(NC)-Pad1)") (class "Default")
      (node (ref "J2") (pin "1") (pinfunction "DAT2(NC)_1") (pintype "bidirectional"))
    )
    (net (code "58") (name "unconnected-(J5-USBID-PadID1)") (class "Default")
      (node (ref "J5") (pin "ID1") (pinfunction "USBID_ID1") (pintype "bidirectional"))
    )
    (net (code "59") (name "unconnected-(U1A-PA5-Pad15)") (class "Default")
      (node (ref "U1") (pin "15") (pinfunction "PA5_15") (pintype "bidirectional"))
    )
    (net (code "60") (name "unconnected-(U1A-PA6-Pad16)") (class "Default")
      (node (ref "U1") (pin "16") (pinfunction "PA6_16") (pintype "bidirectional"))
    )
    (net (code "61") (name "unconnected-(U1A-PA7-Pad17)") (class "Default")
      (node (ref "U1") (pin "17") (pinfunction "PA7_17") (pintype "bidirectional"))
    )
    (net (code "62") (name "unconnected-(U1A-PA15-Pad38)") (class "Default")
      (node (ref "U1") (pin "38") (pinfunction "PA15_38") (pintype "bidirectional"))
    )
    (net (code "63") (name "unconnected-(U1A-PB0-Pad18)") (class "Default")
      (node (ref "U1") (pin "18") (pinfunction "PB0_18") (pintype "bidirectional"))
    )
    (net (code "64") (name "unconnected-(U1A-PB1-Pad19)") (class "Default")
      (node (ref "U1") (pin "19") (pinfunction "PB1_19") (pintype "bidirectional"))
    )
    (net (code "65") (name "unconnected-(U1A-PB2-Pad20)") (class "Default")
      (node (ref "U1") (pin "20") (pinfunction "PB2_20") (pintype "bidirectional"))
    )
    (net (code "66") (name "unconnected-(U1A-PB4-Pad40)") (class "Default")
      (node (ref "U1") (pin "40") (pinfunction "PB4_40") (pintype "bidirectional"))
    )
    (net (code "67") (name "unconnected-(U1A-PB8-Pad45)") (class "Default")
      (node (ref "U1") (pin "45") (pinfunction "PB8_45") (pintype "bidirectional"))
    )
    (net (code "68") (name "unconnected-(U1A-PB9-Pad46)") (class "Default")
      (node (ref "U1") (pin "46") (pinfunction "PB9_46") (pintype "bidirectional"))
    )
    (net (code "69") (name "unconnected-(U1A-PB13-Pad26)") (class "Default")
      (node (ref "U1") (pin "26") (pinfunction "PB13_26") (pintype "bidirectional"))
    )
    (net (code "70") (name "unconnected-(U1A-PC14-OSC32_IN-Pad3)") (class "Default")
      (node (ref "U1") (pin "3") (pinfunction "PC14-OSC32_IN_3") (pintype "bidirectional"))
    )
    (net (code "71") (name "unconnected-(U1A-PC15-OSC32_OUT-Pad4)") (class "Default")
      (node (ref "U1") (pin "4") (pinfunction "PC15-OSC32_OUT_4") (pintype "bidirectional"))
    )
    (net (code "72") (name "unconnected-(U14-Pad3V3)") (class "Default")
      (node (ref "U14") (pin "3V3") (pinfunction "3V3_3V3") (pintype "bidirectional"))
    )
    (net (code "73") (name "unconnected-(U14-PadPB0)") (class "Default")
      (node (ref "U14") (pin "PB0") (pinfunction "PB0_PB0") (pintype "bidirectional"))
    )
    (net (code "74") (name "unconnected-(U14-PadPB1)") (class "Default")
      (node (ref "U14") (pin "PB1") (pinfunction "PB1_PB1") (pintype "bidirectional"))
    )
    (net (code "75") (name "unconnected-(U14-PadPB3)") (class "Default")
      (node (ref "U14") (pin "PB3") (pinfunction "PB3_PB3") (pintype "bidirectional"))
    )
    (net (code "76") (name "unconnected-(U14-PadRST)") (class "Default")
      (node (ref "U14") (pin "RST") (pinfunction "RST_RST") (pintype "bidirectional"))
    )
    (net (code "77") (name "unconnected-(U14-PadSWIM)") (class "Default")
      (node (ref "U14") (pin "SWIM") (pinfunction "SWIM_SWIM") (pintype "bidirectional"))
    )
  )
)
